# TIDA-00620_Schematic.net
KiCad netlist of a schematic drawn in Altium Designer
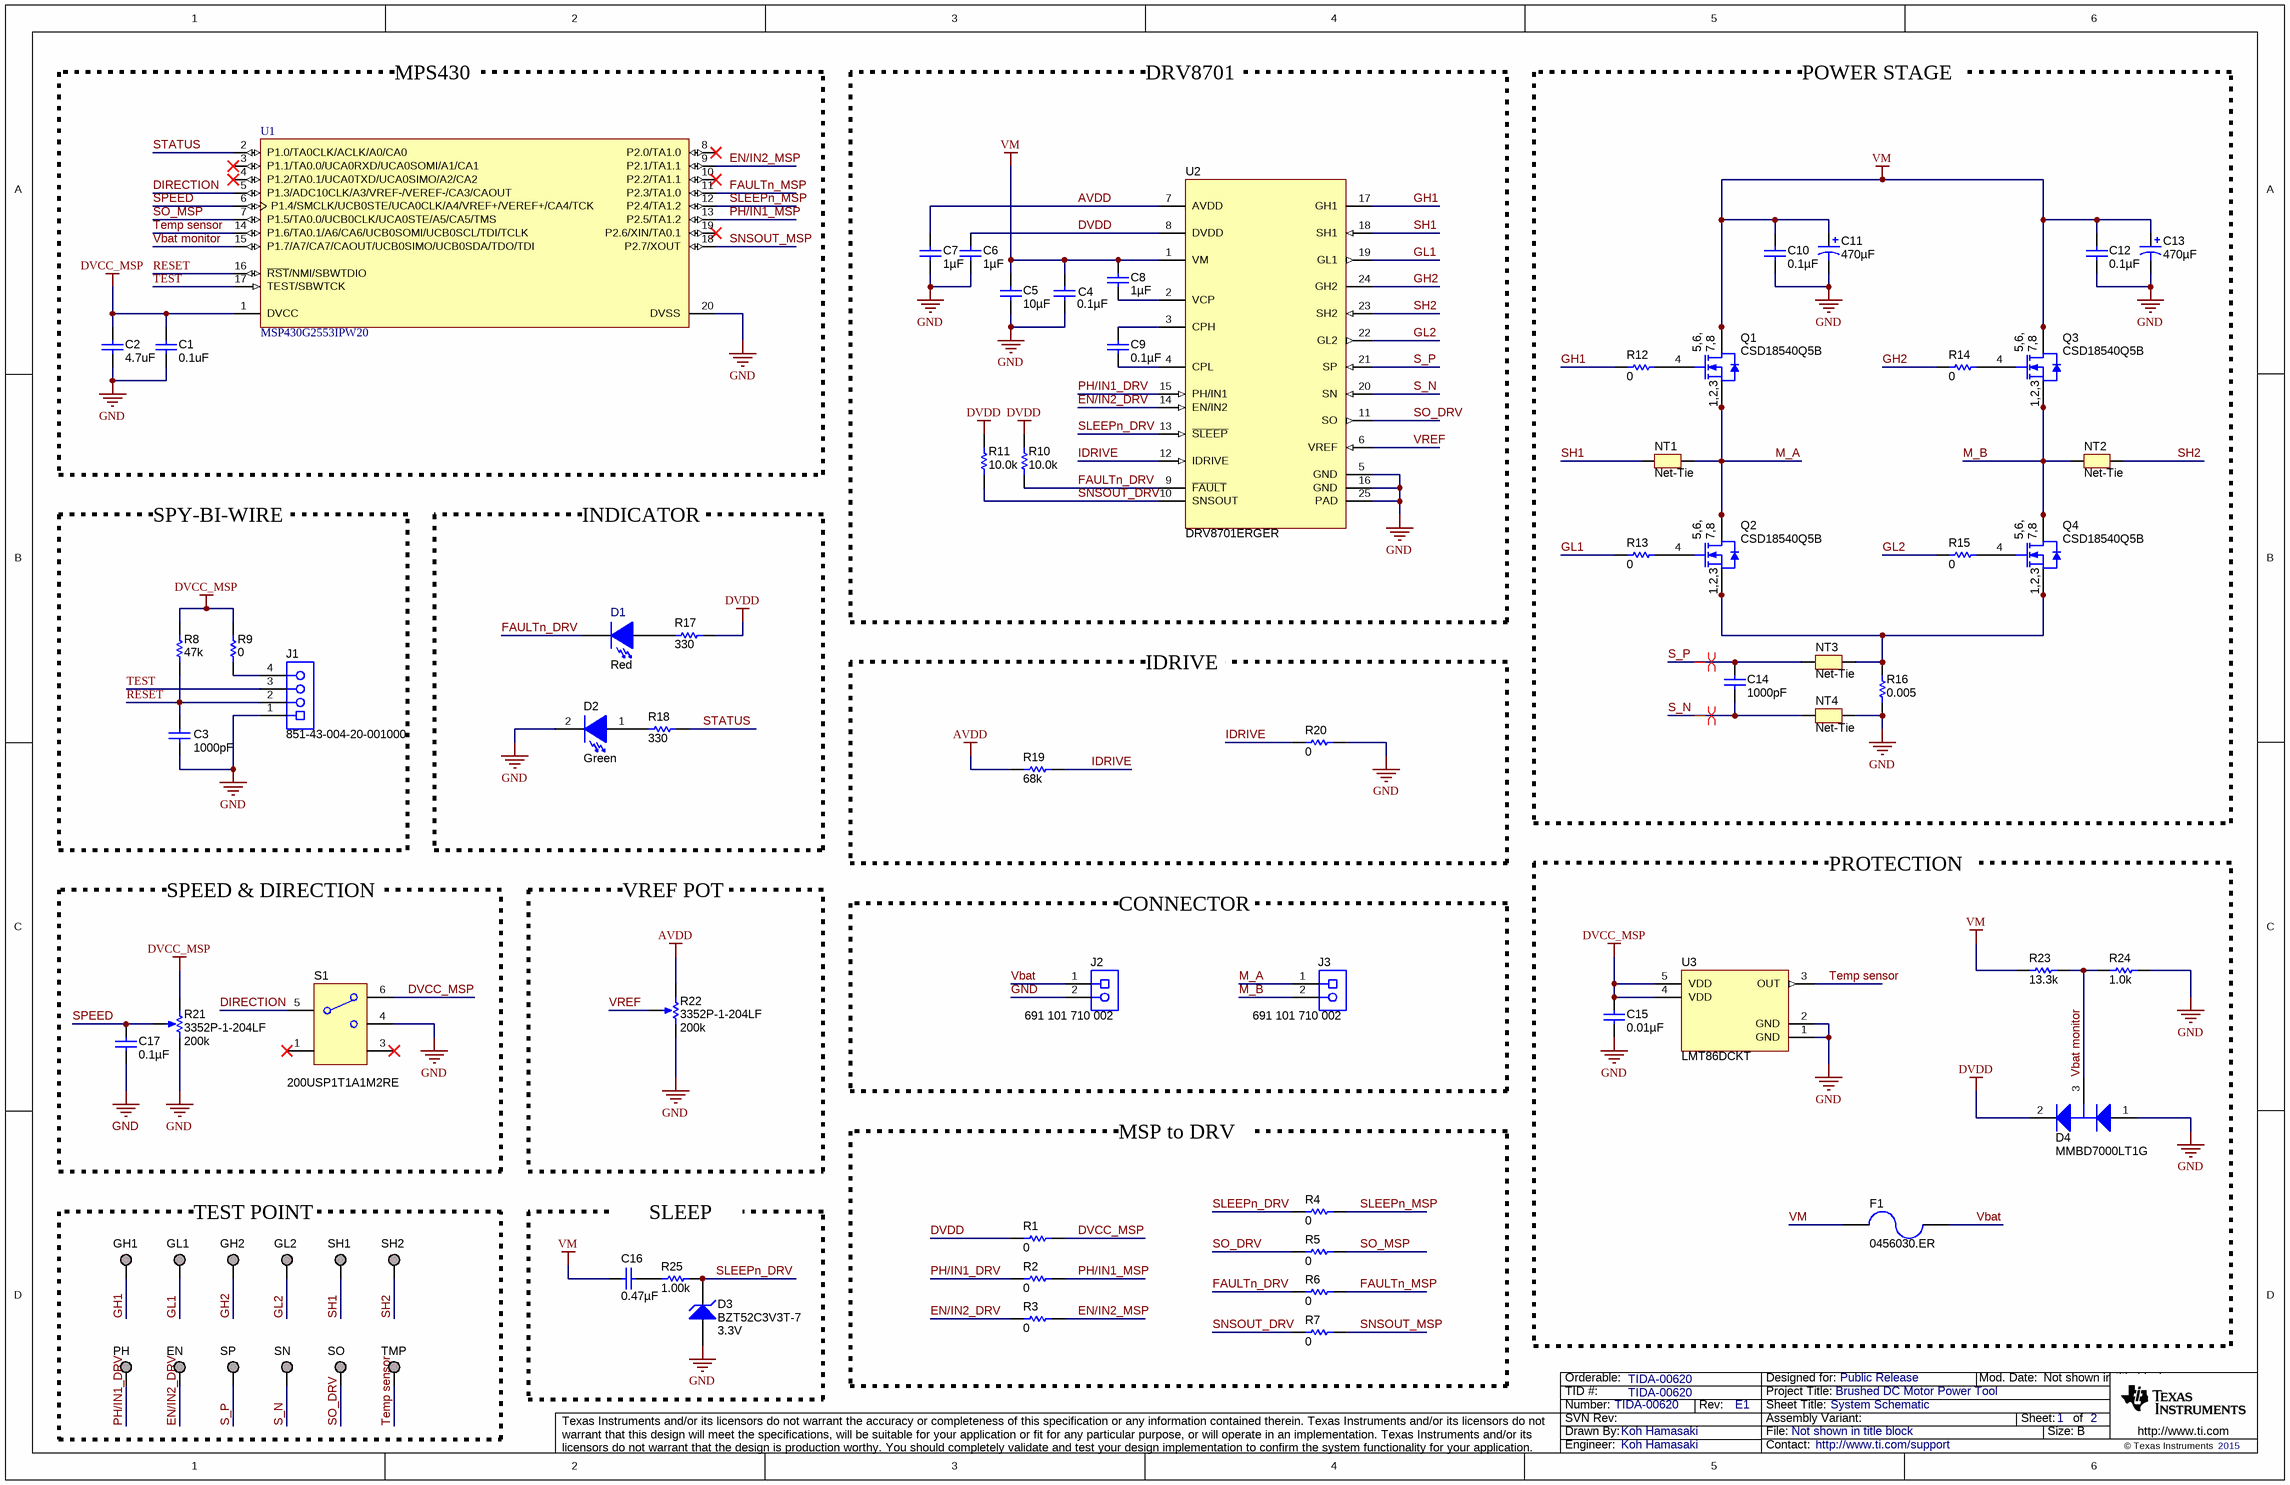
[diagram p0: TIDA-00620_Schematic.SchDoc]

(export (version "E")
  (design (tool "Eeschema 10.0.6"))
  (components
    (comp (ref "C1")
      (value "C0603C104K8RACTU")
      (footprint "0603L")
      (description "CAP, CERM, 0.1uF, 10V, +/-10%, X7R, 0603")
      (fields
        (field (name "VALUEDISPLAYED") "0.1uF")
        (field (name "MANUFACTURER") "Kemet")
        (field (name "PUBLISHER") "Texas Instruments")
      )
      (libsource (lib "Capacitor_Ceramic") (part "C0603C104K8RACTU"))
    )
    (comp (ref "C2")
      (value "C2012X7R1A475M")
      (footprint "0805L")
      (description "CAP, CERM, 4.7uF, 10V, +/-20%, X7R, 0805")
      (fields
        (field (name "VALUEDISPLAYED") "4.7uF")
        (field (name "MANUFACTURER") "TDK")
        (field (name "PUBLISHER") "Texas Instruments")
      )
      (libsource (lib "Capacitor_Ceramic") (part "C2012X7R1A475M"))
    )
    (comp (ref "C3")
      (value "GRM188R71C102KA01D")
      (footprint "0603L")
      (description "CAP, CERM, 1000pF, 16V, +/-10%, X7R, 0603")
      (fields
        (field (name "VALUEDISPLAYED") "1000pF")
        (field (name "MANUFACTURER") "MuRata")
        (field (name "PUBLISHER") "Texas Instruments")
      )
      (libsource (lib "Capacitor_Ceramic") (part "GRM188R71C102KA01D"))
    )
    (comp (ref "C4")
      (value "GRM319R71H104KA01D")
      (footprint "1206L")
      (description "CAP, CERM, 0.1 µF, 50 V, +/- 10%, X7R, 1206")
      (fields
        (field (name "VALUEDISPLAYED") "0.1µF")
        (field (name "MANUFACTURER") "MuRata")
        (field (name "PUBLISHER") "Texas Instruments")
      )
      (libsource (lib "Capacitor_Ceramic") (part "GRM319R71H104KA01D"))
    )
    (comp (ref "C5")
      (value "GRM32ER71H106KA12L")
      (footprint "1210L")
      (description "CAP, CERM, 10 µF, 50 V, +/- 10%, X7R, 1210")
      (fields
        (field (name "VALUEDISPLAYED") "10µF")
        (field (name "MANUFACTURER") "MuRata")
        (field (name "PUBLISHER") "Texas Instruments")
      )
      (libsource (lib "Capacitor_Ceramic") (part "GRM32ER71H106KA12L"))
    )
    (comp (ref "C6")
      (value "GRM188R60J105KA01D")
      (footprint "0603L")
      (description "CAP, CERM, 1 µF, 6.3 V, +/- 10%, X5R, 0603")
      (fields
        (field (name "VALUEDISPLAYED") "1µF")
        (field (name "MANUFACTURER") "MuRata")
        (field (name "PUBLISHER") "Texas Instruments")
      )
      (libsource (lib "Capacitor_Ceramic") (part "GRM188R60J105KA01D"))
    )
    (comp (ref "C7")
      (value "GRM188R60J105KA01D")
      (footprint "0603L")
      (description "CAP, CERM, 1 µF, 6.3 V, +/- 10%, X5R, 0603")
      (fields
        (field (name "VALUEDISPLAYED") "1µF")
        (field (name "MANUFACTURER") "MuRata")
        (field (name "PUBLISHER") "Texas Instruments")
      )
      (libsource (lib "Capacitor_Ceramic") (part "GRM188R60J105KA01D"))
    )
    (comp (ref "C8")
      (value "GRM319R71C105KAA3D")
      (footprint "1206L")
      (description "CAP, CERM, 1 µF, 16 V, +/- 10%, X7R, 1206")
      (fields
        (field (name "VALUEDISPLAYED") "1µF")
        (field (name "MANUFACTURER") "MuRata")
        (field (name "PUBLISHER") "Texas Instruments")
      )
      (libsource (lib "Capacitor_Ceramic") (part "GRM319R71C105KAA3D"))
    )
    (comp (ref "C9")
      (value "GRM155R71C104KA88D")
      (footprint "0402L")
      (description "CAP, CERM, 0.1 µF, 16 V, +/- 10%, X7R, 0402")
      (fields
        (field (name "VALUEDISPLAYED") "0.1µF")
        (field (name "MANUFACTURER") "MuRata")
        (field (name "PUBLISHER") "Texas Instruments")
      )
      (libsource (lib "Capacitor_Ceramic") (part "GRM155R71C104KA88D"))
    )
    (comp (ref "C10")
      (value "GRM319R71H104KA01D")
      (footprint "1206L")
      (description "CAP, CERM, 0.1 µF, 50 V, +/- 10%, X7R, 1206")
      (fields
        (field (name "VALUEDISPLAYED") "0.1µF")
        (field (name "MANUFACTURER") "MuRata")
        (field (name "PUBLISHER") "Texas Instruments")
      )
      (libsource (lib "Capacitor_Ceramic") (part "GRM319R71H104KA01D"))
    )
    (comp (ref "C11")
      (value "EEU-FR1V471LB")
      (footprint "CAPPRD350W60D800H2000")
      (description "CAP, AL, 470 µF, 35 V, +/- 20%, 0.03 ohm, TH")
      (fields
        (field (name "VALUEDISPLAYED") "470µF")
        (field (name "MANUFACTURER") "Panasonic")
        (field (name "PUBLISHER") "Texas Instruments")
      )
      (libsource (lib "Capacitor_Aluminum") (part "EEU-FR1V471LB"))
    )
    (comp (ref "C12")
      (value "GRM319R71H104KA01D")
      (footprint "1206L")
      (description "CAP, CERM, 0.1 µF, 50 V, +/- 10%, X7R, 1206")
      (fields
        (field (name "VALUEDISPLAYED") "0.1µF")
        (field (name "MANUFACTURER") "MuRata")
        (field (name "PUBLISHER") "Texas Instruments")
      )
      (libsource (lib "Capacitor_Ceramic") (part "GRM319R71H104KA01D"))
    )
    (comp (ref "C13")
      (value "EEU-FR1V471LB")
      (footprint "CAPPRD350W60D800H2000")
      (description "CAP, AL, 470 µF, 35 V, +/- 20%, 0.03 ohm, TH")
      (fields
        (field (name "VALUEDISPLAYED") "470µF")
        (field (name "MANUFACTURER") "Panasonic")
        (field (name "PUBLISHER") "Texas Instruments")
      )
      (libsource (lib "Capacitor_Aluminum") (part "EEU-FR1V471LB"))
    )
    (comp (ref "C14")
      (value "GRM155R71C102KA01D")
      (footprint "0402L")
      (description "CAP, CERM, 1000pF, 16V, +/-10%, X7R, 0402")
      (fields
        (field (name "VALUEDISPLAYED") "1000pF")
        (field (name "MANUFACTURER") "MuRata")
        (field (name "PUBLISHER") "Texas Instruments")
      )
      (libsource (lib "Capacitor_Ceramic") (part "GRM155R71C102KA01D"))
    )
    (comp (ref "C15")
      (value "GRM188R70J103KA01D")
      (footprint "0603L")
      (description "CAP, CERM, 0.01 µF, 6.3 V, +/- 10%, X7R, 0603")
      (fields
        (field (name "VALUEDISPLAYED") "0.01µF")
        (field (name "MANUFACTURER") "MuRata")
        (field (name "PUBLISHER") "Texas Instruments")
      )
      (libsource (lib "Capacitor_Ceramic") (part "GRM188R70J103KA01D"))
    )
    (comp (ref "C16")
      (value "GRM155R61A474KE15D")
      (footprint "0402L")
      (description "CAP, CERM, 0.47 µF, 10 V, +/- 10%, X5R, 0402")
      (fields
        (field (name "VALUEDISPLAYED") "0.47µF")
        (field (name "MANUFACTURER") "MuRata")
        (field (name "PUBLISHER") "Texas Instruments")
      )
      (libsource (lib "Capacitor_Ceramic") (part "GRM155R61A474KE15D"))
    )
    (comp (ref "C17")
      (value "GCM155R71C104KA55D")
      (footprint "0402")
      (description "CAP, CERM, 0.1 µF, 16 V, +/- 10%, X7R, 0402")
      (fields
        (field (name "VALUEDISPLAYED") "0.1µF")
        (field (name "MANUFACTURER") "MuRata")
        (field (name "PUBLISHER") "Texas Instruments")
      )
      (libsource (lib "Capacitor_Ceramic") (part "GCM155R71C104KA55D"))
    )
    (comp (ref "D1")
      (value "Red")
      (footprint "LED_LTST-C170")
      (description "LED, Red, SMD")
      (fields
        (field (name "MANUFACTURER") "Lite-On")
        (field (name "PARTNUMBER") "LTST-C170KRKT")
        (field (name "PUBLISHER") "Texas Instruments")
      )
      (libsource (lib "LED") (part "LTST-C170KRKT"))
    )
    (comp (ref "D2")
      (value "Green")
      (footprint "LED_LTST-C171")
      (description "LED, Green, SMD")
      (fields
        (field (name "MANUFACTURER") "Lite-On")
        (field (name "PARTNUMBER") "LTST-C171GKT")
        (field (name "PUBLISHER") "Texas Instruments")
      )
      (libsource (lib "LED") (part "LTST-C171GKT"))
    )
    (comp (ref "D3")
      (value "BZT52C3V3T-7")
      (footprint "SOD-523")
      (description "Diode, Zener, 3.3 V, 300 mW, SOD-523")
      (fields
        (field (name "ALTIUM_VALUE") "3.3V")
        (field (name "MANUFACTURER") "Diodes Inc.")
        (field (name "SYMBOLCREATOR") "a0412235")
        (field (name "PUBLISHER") "Texas Instruments")
      )
      (libsource (lib "ZenerDiodes") (part "BZT52C3V3T-7"))
    )
    (comp (ref "D4")
      (value "MMBD7000LT1G")
      (footprint "SOT-23")
      (description "Diode, Switching, 100 V, 0.2 A, SOT-23")
      (fields (field (name "MANUFACTURER") "ON Semiconductor") (field (name "PUBLISHER") "Texas Instruments"))
      (libsource (lib "Diode") (part "MMBD7000LT1G"))
    )
    (comp (ref "EN")
      (value "TESTPOINT")
      (footprint "TP_25MIL-SMT")
      (description "TEST POINT.  No entry in BOM.")
      (fields (field (name "PUBLISHER") "Texas Instruments"))
      (libsource (lib "MiscParts") (part "TESTPOINT"))
    )
    (comp (ref "F1")
      (value "0456030.ER")
      (footprint "FUSE_0456030")
      (description "Fuse, 30 A, 72 V, SMD")
      (fields (field (name "MANUFACTURER") "Littelfuse") (field (name "PUBLISHER") "Texas Instruments"))
      (libsource (lib "Fuse") (part "0456030.ER"))
    )
    (comp (ref "GH1")
      (value "TESTPOINT")
      (footprint "TP_25MIL-SMT")
      (description "TEST POINT.  No entry in BOM.")
      (fields (field (name "PUBLISHER") "Texas Instruments"))
      (libsource (lib "MiscParts") (part "TESTPOINT"))
    )
    (comp (ref "GH2")
      (value "TESTPOINT")
      (footprint "TP_25MIL-SMT")
      (description "TEST POINT.  No entry in BOM.")
      (fields (field (name "PUBLISHER") "Texas Instruments"))
      (libsource (lib "MiscParts") (part "TESTPOINT"))
    )
    (comp (ref "GL1")
      (value "TESTPOINT")
      (footprint "TP_25MIL-SMT")
      (description "TEST POINT.  No entry in BOM.")
      (fields (field (name "PUBLISHER") "Texas Instruments"))
      (libsource (lib "MiscParts") (part "TESTPOINT"))
    )
    (comp (ref "GL2")
      (value "TESTPOINT")
      (footprint "TP_25MIL-SMT")
      (description "TEST POINT.  No entry in BOM.")
      (fields (field (name "PUBLISHER") "Texas Instruments"))
      (libsource (lib "MiscParts") (part "TESTPOINT"))
    )
    (comp (ref "J1")
      (value "851-43-004-20-001000")
      (footprint "CONN_851-43-004-20-001000")
      (description "SOCKET .050\" GRID SIP 4 POS R/A, TH")
      (fields
        (field (name "MANUFACTURER") "Mill-Max")
        (field (name "SYMBOLCREATOR") "a0411947")
        (field (name "PUBLISHER") "Texas Instruments")
      )
      (libsource (lib "Connectors_Mill_Max") (part "851-43-004-20-001000"))
    )
    (comp (ref "J2")
      (value "691 101 710 002")
      (footprint "Wurth_691101710002")
      (description "Terminal Block, 5 mm, 2x1, Tin, TH")
      (fields
        (field (name "MANUFACTURER") "Wurth Elektronik")
        (field (name "SYMBOLCREATOR") "a0412235")
        (field (name "PUBLISHER") "Texas Instruments")
      )
      (libsource (lib "Connectors_Other") (part "691 101 710 002"))
    )
    (comp (ref "J3")
      (value "691 101 710 002")
      (footprint "Wurth_691101710002")
      (description "Terminal Block, 5 mm, 2x1, Tin, TH")
      (fields
        (field (name "MANUFACTURER") "Wurth Elektronik")
        (field (name "SYMBOLCREATOR") "a0412235")
        (field (name "PUBLISHER") "Texas Instruments")
      )
      (libsource (lib "Connectors_Other") (part "691 101 710 002"))
    )
    (comp (ref "NT1")
      (value "Net-Tie")
      (footprint "Net-Tie_10milWide_30milLong")
      (description "Single point connection between nets.")
      (fields (field (name "SYMBOLCREATOR") "codlsc") (field (name "PUBLISHER") "Texas Instruments"))
      (libsource (lib "MiscParts") (part "Net-Tie"))
    )
    (comp (ref "NT2")
      (value "Net-Tie")
      (footprint "Net-Tie_10milWide_30milLong")
      (description "Single point connection between nets.")
      (fields (field (name "SYMBOLCREATOR") "codlsc") (field (name "PUBLISHER") "Texas Instruments"))
      (libsource (lib "MiscParts") (part "Net-Tie"))
    )
    (comp (ref "NT3")
      (value "Net-Tie")
      (footprint "Net-Tie_10milWide_30milLong")
      (description "Single point connection between nets.")
      (fields (field (name "SYMBOLCREATOR") "codlsc") (field (name "PUBLISHER") "Texas Instruments"))
      (libsource (lib "MiscParts") (part "Net-Tie"))
    )
    (comp (ref "NT4")
      (value "Net-Tie")
      (footprint "Net-Tie_10milWide_30milLong")
      (description "Single point connection between nets.")
      (fields (field (name "SYMBOLCREATOR") "codlsc") (field (name "PUBLISHER") "Texas Instruments"))
      (libsource (lib "MiscParts") (part "Net-Tie"))
    )
    (comp (ref "PH")
      (value "TESTPOINT")
      (footprint "TP_25MIL-SMT")
      (description "TEST POINT.  No entry in BOM.")
      (fields (field (name "PUBLISHER") "Texas Instruments"))
      (libsource (lib "MiscParts") (part "TESTPOINT"))
    )
    (comp (ref "Q1")
      (value "CSD18540Q5B")
      (footprint "TRANS_NexFET_Q5B")
      (description "MOSFET, N-CH, 60 V, 28 A, SON 5x6mm")
      (fields
        (field (name "MANUFACTURER") "Texas Instruments")
        (field (name "PUBLISHER") "Texas Instruments")
      )
      (libsource (lib "FETs") (part "CSD18540Q5B"))
    )
    (comp (ref "Q2")
      (value "CSD18540Q5B")
      (footprint "TRANS_NexFET_Q5B")
      (description "MOSFET, N-CH, 60 V, 28 A, SON 5x6mm")
      (fields
        (field (name "MANUFACTURER") "Texas Instruments")
        (field (name "PUBLISHER") "Texas Instruments")
      )
      (libsource (lib "FETs") (part "CSD18540Q5B"))
    )
    (comp (ref "Q3")
      (value "CSD18540Q5B")
      (footprint "TRANS_NexFET_Q5B")
      (description "MOSFET, N-CH, 60 V, 28 A, SON 5x6mm")
      (fields
        (field (name "MANUFACTURER") "Texas Instruments")
        (field (name "PUBLISHER") "Texas Instruments")
      )
      (libsource (lib "FETs") (part "CSD18540Q5B"))
    )
    (comp (ref "Q4")
      (value "CSD18540Q5B")
      (footprint "TRANS_NexFET_Q5B")
      (description "MOSFET, N-CH, 60 V, 28 A, SON 5x6mm")
      (fields
        (field (name "MANUFACTURER") "Texas Instruments")
        (field (name "PUBLISHER") "Texas Instruments")
      )
      (libsource (lib "FETs") (part "CSD18540Q5B"))
    )
    (comp (ref "R1")
      (value "CRCW04020000Z0ED")
      (footprint "0402L")
      (description "RES, 0, 5%, 0.063 W, 0402")
      (fields
        (field (name "VALUEDISPLAYED") "0")
        (field (name "MANUFACTURER") "Vishay-Dale")
        (field (name "PUBLISHER") "Texas Instruments")
      )
      (libsource (lib "Resistor_0402") (part "CRCW04020000Z0ED"))
    )
    (comp (ref "R2")
      (value "CRCW04020000Z0ED")
      (footprint "0402L")
      (description "RES, 0, 5%, 0.063 W, 0402")
      (fields
        (field (name "VALUEDISPLAYED") "0")
        (field (name "MANUFACTURER") "Vishay-Dale")
        (field (name "PUBLISHER") "Texas Instruments")
      )
      (libsource (lib "Resistor_0402") (part "CRCW04020000Z0ED"))
    )
    (comp (ref "R3")
      (value "CRCW04020000Z0ED")
      (footprint "0402L")
      (description "RES, 0, 5%, 0.063 W, 0402")
      (fields
        (field (name "VALUEDISPLAYED") "0")
        (field (name "MANUFACTURER") "Vishay-Dale")
        (field (name "PUBLISHER") "Texas Instruments")
      )
      (libsource (lib "Resistor_0402") (part "CRCW04020000Z0ED"))
    )
    (comp (ref "R4")
      (value "CRCW04020000Z0ED")
      (footprint "0402L")
      (description "RES, 0, 5%, 0.063 W, 0402")
      (fields
        (field (name "VALUEDISPLAYED") "0")
        (field (name "MANUFACTURER") "Vishay-Dale")
        (field (name "PUBLISHER") "Texas Instruments")
      )
      (libsource (lib "Resistor_0402") (part "CRCW04020000Z0ED"))
    )
    (comp (ref "R5")
      (value "CRCW04020000Z0ED")
      (footprint "0402L")
      (description "RES, 0, 5%, 0.063 W, 0402")
      (fields
        (field (name "VALUEDISPLAYED") "0")
        (field (name "MANUFACTURER") "Vishay-Dale")
        (field (name "PUBLISHER") "Texas Instruments")
      )
      (libsource (lib "Resistor_0402") (part "CRCW04020000Z0ED"))
    )
    (comp (ref "R6")
      (value "CRCW04020000Z0ED")
      (footprint "0402L")
      (description "RES, 0, 5%, 0.063 W, 0402")
      (fields
        (field (name "VALUEDISPLAYED") "0")
        (field (name "MANUFACTURER") "Vishay-Dale")
        (field (name "PUBLISHER") "Texas Instruments")
      )
      (libsource (lib "Resistor_0402") (part "CRCW04020000Z0ED"))
    )
    (comp (ref "R7")
      (value "CRCW04020000Z0ED")
      (footprint "0402L")
      (description "RES, 0, 5%, 0.063 W, 0402")
      (fields
        (field (name "VALUEDISPLAYED") "0")
        (field (name "MANUFACTURER") "Vishay-Dale")
        (field (name "PUBLISHER") "Texas Instruments")
      )
      (libsource (lib "Resistor_0402") (part "CRCW04020000Z0ED"))
    )
    (comp (ref "R8")
      (value "47k")
      (footprint "0603L")
      (description "RES, 47k ohm, 5%, 0.1W, 0603")
      (fields
        (field (name "PARTNUMBER") "CRCW060347K0JNEA")
        (field (name "MANUFACTURER") "Vishay-Dale")
        (field (name "PUBLISHER") "Texas Instruments")
      )
      (libsource (lib "Resistor_0603") (part "CRCW060347K0JNEA"))
    )
    (comp (ref "R9")
      (value "0")
      (footprint "0603L")
      (description "RES, 0 ohm, 5%, 0.1W, 0603")
      (fields
        (field (name "PARTNUMBER") "CRCW06030000Z0EA")
        (field (name "MANUFACTURER") "Vishay-Dale")
        (field (name "PUBLISHER") "Texas Instruments")
      )
      (libsource (lib "Resistor_0603") (part "CRCW06030000Z0EA"))
    )
    (comp (ref "R10")
      (value "ERJ-2RKF1002X")
      (footprint "0402L")
      (description "RES, 10.0 k, 1%, 0.1 W, 0402")
      (fields
        (field (name "VALUEDISPLAYED") "10.0k")
        (field (name "MANUFACTURER") "Panasonic")
        (field (name "PUBLISHER") "Texas Instruments")
      )
      (libsource (lib "Resistor_0402") (part "ERJ-2RKF1002X"))
    )
    (comp (ref "R11")
      (value "ERJ-2RKF1002X")
      (footprint "0402L")
      (description "RES, 10.0 k, 1%, 0.1 W, 0402")
      (fields
        (field (name "VALUEDISPLAYED") "10.0k")
        (field (name "MANUFACTURER") "Panasonic")
        (field (name "PUBLISHER") "Texas Instruments")
      )
      (libsource (lib "Resistor_0402") (part "ERJ-2RKF1002X"))
    )
    (comp (ref "R12")
      (value "CRCW04020000Z0ED")
      (footprint "0402L")
      (description "RES, 0, 5%, 0.063 W, 0402")
      (fields
        (field (name "VALUEDISPLAYED") "0")
        (field (name "MANUFACTURER") "Vishay-Dale")
        (field (name "PUBLISHER") "Texas Instruments")
      )
      (libsource (lib "Resistor_0402") (part "CRCW04020000Z0ED"))
    )
    (comp (ref "R13")
      (value "CRCW04020000Z0ED")
      (footprint "0402L")
      (description "RES, 0, 5%, 0.063 W, 0402")
      (fields
        (field (name "VALUEDISPLAYED") "0")
        (field (name "MANUFACTURER") "Vishay-Dale")
        (field (name "PUBLISHER") "Texas Instruments")
      )
      (libsource (lib "Resistor_0402") (part "CRCW04020000Z0ED"))
    )
    (comp (ref "R14")
      (value "CRCW04020000Z0ED")
      (footprint "0402L")
      (description "RES, 0, 5%, 0.063 W, 0402")
      (fields
        (field (name "VALUEDISPLAYED") "0")
        (field (name "MANUFACTURER") "Vishay-Dale")
        (field (name "PUBLISHER") "Texas Instruments")
      )
      (libsource (lib "Resistor_0402") (part "CRCW04020000Z0ED"))
    )
    (comp (ref "R15")
      (value "CRCW04020000Z0ED")
      (footprint "0402L")
      (description "RES, 0, 5%, 0.063 W, 0402")
      (fields
        (field (name "VALUEDISPLAYED") "0")
        (field (name "MANUFACTURER") "Vishay-Dale")
        (field (name "PUBLISHER") "Texas Instruments")
      )
      (libsource (lib "Resistor_0402") (part "CRCW04020000Z0ED"))
    )
    (comp (ref "R16")
      (value "KRL11050-C-R005-F-T1")
      (footprint "4320")
      (description "RES, 0.005, 1%, 6 W, 4320_WIDE")
      (fields
        (field (name "VALUEDISPLAYED") "0.005")
        (field (name "MANUFACTURER") "Susumu Co Ltd")
        (field (name "PUBLISHER") "Texas Instruments")
      )
      (libsource (lib "Resistor_OtherSMT") (part "KRL11050-C-R005-F-T1"))
    )
    (comp (ref "R17")
      (value "RC0603FR-07330RL")
      (footprint "0603L")
      (description "RES, 330, 1%, 0.1 W, 0603")
      (fields
        (field (name "VALUEDISPLAYED") "330")
        (field (name "MANUFACTURER") "Yageo America")
        (field (name "PUBLISHER") "Texas Instruments")
      )
      (libsource (lib "Resistor_0603") (part "RC0603FR-07330RL"))
    )
    (comp (ref "R18")
      (value "RC0603FR-07330RL")
      (footprint "0603L")
      (description "RES, 330, 1%, 0.1 W, 0603")
      (fields
        (field (name "VALUEDISPLAYED") "330")
        (field (name "MANUFACTURER") "Yageo America")
        (field (name "PUBLISHER") "Texas Instruments")
      )
      (libsource (lib "Resistor_0603") (part "RC0603FR-07330RL"))
    )
    (comp (ref "R19")
      (value "CRCW040268K0JNED")
      (footprint "0402")
      (description "RES, 68 k, 5%, 0.063 W, 0402")
      (fields
        (field (name "VALUEDISPLAYED") "68k")
        (field (name "MANUFACTURER") "Vishay-Dale")
        (field (name "PUBLISHER") "Texas Instruments")
      )
      (libsource (lib "Resistor_0402") (part "CRCW040268K0JNED"))
    )
    (comp (ref "R20")
      (value "CRCW04020000Z0ED")
      (footprint "0402L")
      (description "RES, 0, 5%, 0.063 W, 0402")
      (fields
        (field (name "VALUEDISPLAYED") "0")
        (field (name "MANUFACTURER") "Vishay-Dale")
        (field (name "PUBLISHER") "Texas Instruments")
      )
      (libsource (lib "Resistor_0402") (part "CRCW04020000Z0ED"))
    )
    (comp (ref "R21")
      (value "3352P-1-204LF")
      (footprint "Bourns_3352P")
      (description "Trimmer, 200 K, 0.5 W, TH")
      (fields
        (field (name "ALTIUM_VALUE") "200k")
        (field (name "MANUFACTURER") "Bourns")
        (field (name "SYMBOLCREATOR") "a0412235")
        (field (name "PUBLISHER") "Texas Instruments")
      )
      (libsource (lib "Other_Passive") (part "3352P-1-204LF"))
    )
    (comp (ref "R22")
      (value "3352P-1-204LF")
      (footprint "Bourns_3352P")
      (description "Trimmer, 200 K, 0.5 W, TH")
      (fields
        (field (name "ALTIUM_VALUE") "200k")
        (field (name "MANUFACTURER") "Bourns")
        (field (name "SYMBOLCREATOR") "a0412235")
        (field (name "PUBLISHER") "Texas Instruments")
      )
      (libsource (lib "Other_Passive") (part "3352P-1-204LF"))
    )
    (comp (ref "R23")
      (value "CRCW040213K3FKED")
      (footprint "0402L")
      (description "RES, 13.3 k, 1%, 0.063 W, 0402")
      (fields
        (field (name "VALUEDISPLAYED") "13.3k")
        (field (name "MANUFACTURER") "Vishay-Dale")
        (field (name "PUBLISHER") "Texas Instruments")
      )
      (libsource (lib "Resistor_0402") (part "CRCW040213K3FKED"))
    )
    (comp (ref "R24")
      (value "CRCW04021K00JNED")
      (footprint "0402L")
      (description "RES, 1.0 k, 5%, 0.063 W, 0402")
      (fields
        (field (name "VALUEDISPLAYED") "1.0k")
        (field (name "MANUFACTURER") "Vishay-Dale")
        (field (name "PUBLISHER") "Texas Instruments")
      )
      (libsource (lib "Resistor_0402") (part "CRCW04021K00JNED"))
    )
    (comp (ref "R25")
      (value "CRCW04021K00FKED")
      (footprint "0402L")
      (description "RES, 1.00 k, 1%, 0.063 W, 0402")
      (fields
        (field (name "MANUFACTURER") "Vishay-Dale")
        (field (name "VALUEDISPLAYED") "1.00k")
        (field (name "PUBLISHER") "Texas Instruments")
      )
      (libsource (lib "Resistor_0402") (part "CRCW04021K00FKED"))
    )
    (comp (ref "S1")
      (value "200USP1T1A1M2RE")
      (footprint "SW_200USP1T1A1M2")
      (description "Switch, SPDT, On-On, 2 Pos, TH")
      (fields
        (field (name "MANUFACTURER") "E-Switch")
        (field (name "SYMBOLCREATOR") "Altium")
        (field (name "PUBLISHER") "Texas Instruments")
      )
      (libsource (lib "Switches") (part "200USP1T1A1M2RE"))
    )
    (comp (ref "SH1")
      (value "TESTPOINT")
      (footprint "TP_25MIL-SMT")
      (description "TEST POINT.  No entry in BOM.")
      (fields (field (name "PUBLISHER") "Texas Instruments"))
      (libsource (lib "MiscParts") (part "TESTPOINT"))
    )
    (comp (ref "SH2")
      (value "TESTPOINT")
      (footprint "TP_25MIL-SMT")
      (description "TEST POINT.  No entry in BOM.")
      (fields (field (name "PUBLISHER") "Texas Instruments"))
      (libsource (lib "MiscParts") (part "TESTPOINT"))
    )
    (comp (ref "SN")
      (value "TESTPOINT")
      (footprint "TP_25MIL-SMT")
      (description "TEST POINT.  No entry in BOM.")
      (fields (field (name "PUBLISHER") "Texas Instruments"))
      (libsource (lib "MiscParts") (part "TESTPOINT"))
    )
    (comp (ref "SO")
      (value "TESTPOINT")
      (footprint "TP_25MIL-SMT")
      (description "TEST POINT.  No entry in BOM.")
      (fields (field (name "PUBLISHER") "Texas Instruments"))
      (libsource (lib "MiscParts") (part "TESTPOINT"))
    )
    (comp (ref "SP")
      (value "TESTPOINT")
      (footprint "TP_25MIL-SMT")
      (description "TEST POINT.  No entry in BOM.")
      (fields (field (name "PUBLISHER") "Texas Instruments"))
      (libsource (lib "MiscParts") (part "TESTPOINT"))
    )
    (comp (ref "TMP")
      (value "TESTPOINT")
      (footprint "TP_25MIL-SMT")
      (description "TEST POINT.  No entry in BOM.")
      (fields (field (name "PUBLISHER") "Texas Instruments"))
      (libsource (lib "MiscParts") (part "TESTPOINT"))
    )
    (comp (ref "U1")
      (value "MSP430G2553IPW20")
      (footprint "PW0020A_N")
      (fields
        (field (name "ALTERNATE PARTNUMBER") "Equivalent")
        (field (name "MANUFACTURER") "Texas Instruments")
      )
      (libsource (lib "TI MCU MSP430") (part "MSP430G2553IPW20"))
    )
    (comp (ref "U2")
      (value "DRV8701ERGER")
      (footprint "RGE0024F")
      (description "H-Bridge Gate Driver, RGE0024F")
      (fields
        (field (name "ALTERNATE PARTNUMBER") "DRV8701ERGET")
        (field (name "MANUFACTURER") "Texas Instruments")
        (field (name "SYMBOLCREATOR") "Altium")
        (field (name "PUBLISHER") "Texas Instruments")
      )
      (libsource (lib "TI_Pre_RTM") (part "DRV8701ERGER"))
    )
    (comp (ref "U3")
      (value "LMT86DCKT")
      (footprint "DCK0005A_N")
      (description "Analog Temperature Sensors with Class-AB Output, DCK0005A")
      (fields
        (field (name "MANUFACTURER") "Texas Instruments")
        (field (name "SYMBOLCREATOR") "a0799628")
        (field (name "PUBLISHER") "Texas Instruments")
      )
      (libsource (lib "TI_Pre_Release") (part "LMT86DCKT"))
    )
  )
  (nets
    (net (code "1") (name "/DIRECTION") (class "Default")
      (node (ref "S1") (pin "5") (pinfunction "COM_5") (pintype "passive"))
      (node (ref "U1") (pin "5") (pinfunction "P1.3/ADC10CLK/A3/VREF-/VEREF-/CA3/CAOUT_5") (pintype "bidirectional"))
    )
    (net (code "2") (name "/EN{slash}IN2_DRV") (class "Default")
      (node (ref "EN") (pin "1") (pintype "passive"))
      (node (ref "R3") (pin "1") (pinfunction "1_1") (pintype "passive"))
      (node (ref "U2") (pin "14") (pinfunction "EN/IN2_14") (pintype "input"))
    )
    (net (code "3") (name "/EN{slash}IN2_MSP") (class "Default")
      (node (ref "R3") (pin "2") (pinfunction "2_2") (pintype "passive"))
      (node (ref "U1") (pin "9") (pinfunction "P2.1/TA1.1_9") (pintype "bidirectional"))
    )
    (net (code "4") (name "/FAULTn_DRV") (class "Default")
      (node (ref "D1") (pin "2") (pinfunction "K_2") (pintype "passive"))
      (node (ref "R10") (pin "1") (pinfunction "1_1") (pintype "passive"))
      (node (ref "R6") (pin "1") (pinfunction "1_1") (pintype "passive"))
      (node (ref "U2") (pin "9") (pinfunction "FAULT_9") (pintype "open_collector"))
    )
    (net (code "5") (name "/FAULTn_MSP") (class "Default")
      (node (ref "R6") (pin "2") (pinfunction "2_2") (pintype "passive"))
      (node (ref "U1") (pin "11") (pinfunction "P2.3/TA1.0_11") (pintype "bidirectional"))
    )
    (net (code "6") (name "/GH1") (class "Default")
      (node (ref "GH1") (pin "1") (pintype "passive"))
      (node (ref "R12") (pin "1") (pinfunction "1_1") (pintype "passive"))
      (node (ref "U2") (pin "17") (pinfunction "GH1_17") (pintype "power_in"))
    )
    (net (code "7") (name "/GH2") (class "Default")
      (node (ref "GH2") (pin "1") (pintype "passive"))
      (node (ref "R14") (pin "1") (pinfunction "1_1") (pintype "passive"))
      (node (ref "U2") (pin "24") (pinfunction "GH2_24") (pintype "power_in"))
    )
    (net (code "8") (name "/GL1") (class "Default")
      (node (ref "GL1") (pin "1") (pintype "passive"))
      (node (ref "R13") (pin "1") (pinfunction "1_1") (pintype "passive"))
      (node (ref "U2") (pin "19") (pinfunction "GL1_19") (pintype "output"))
    )
    (net (code "9") (name "/GL2") (class "Default")
      (node (ref "GL2") (pin "1") (pintype "passive"))
      (node (ref "R15") (pin "1") (pinfunction "1_1") (pintype "passive"))
      (node (ref "U2") (pin "22") (pinfunction "GL2_22") (pintype "output"))
    )
    (net (code "10") (name "/IDRIVE") (class "Default")
      (node (ref "R19") (pin "2") (pinfunction "2_2") (pintype "passive"))
      (node (ref "R20") (pin "1") (pinfunction "1_1") (pintype "passive"))
      (node (ref "U2") (pin "12") (pinfunction "IDRIVE_12") (pintype "input"))
    )
    (net (code "11") (name "/M_A") (class "Default")
      (node (ref "J3") (pin "1") (pinfunction "1_1") (pintype "passive"))
      (node (ref "NT1") (pin "2") (pinfunction "2_2") (pintype "passive"))
      (node (ref "Q1") (pin "1") (pinfunction "S_1") (pintype "passive"))
      (node (ref "Q1") (pin "2") (pinfunction "S_2") (pintype "passive"))
      (node (ref "Q1") (pin "3") (pinfunction "S_3") (pintype "passive"))
      (node (ref "Q2") (pin "5") (pinfunction "D_5") (pintype "passive"))
      (node (ref "Q2") (pin "6") (pinfunction "D_6") (pintype "passive"))
      (node (ref "Q2") (pin "7") (pinfunction "D_7") (pintype "passive"))
      (node (ref "Q2") (pin "8") (pinfunction "D_8") (pintype "passive"))
    )
    (net (code "12") (name "/M_B") (class "Default")
      (node (ref "J3") (pin "2") (pinfunction "2_2") (pintype "passive"))
      (node (ref "NT2") (pin "1") (pinfunction "1_1") (pintype "passive"))
      (node (ref "Q3") (pin "1") (pinfunction "S_1") (pintype "passive"))
      (node (ref "Q3") (pin "2") (pinfunction "S_2") (pintype "passive"))
      (node (ref "Q3") (pin "3") (pinfunction "S_3") (pintype "passive"))
      (node (ref "Q4") (pin "5") (pinfunction "D_5") (pintype "passive"))
      (node (ref "Q4") (pin "6") (pinfunction "D_6") (pintype "passive"))
      (node (ref "Q4") (pin "7") (pinfunction "D_7") (pintype "passive"))
      (node (ref "Q4") (pin "8") (pinfunction "D_8") (pintype "passive"))
    )
    (net (code "13") (name "/PH{slash}IN1_DRV") (class "Default")
      (node (ref "PH") (pin "1") (pintype "passive"))
      (node (ref "R2") (pin "1") (pinfunction "1_1") (pintype "passive"))
      (node (ref "U2") (pin "15") (pinfunction "PH/IN1_15") (pintype "input"))
    )
    (net (code "14") (name "/PH{slash}IN1_MSP") (class "Default")
      (node (ref "R2") (pin "2") (pinfunction "2_2") (pintype "passive"))
      (node (ref "U1") (pin "13") (pinfunction "P2.5/TA1.2_13") (pintype "bidirectional"))
    )
    (net (code "15") (name "/RESET") (class "Default")
      (node (ref "C3") (pin "1") (pinfunction "1_1") (pintype "passive"))
      (node (ref "J1") (pin "2") (pinfunction "2_2") (pintype "passive"))
      (node (ref "R8") (pin "1") (pinfunction "1_1") (pintype "passive"))
      (node (ref "U1") (pin "16") (pinfunction "~{RST}/NMI/SBWTDIO_16") (pintype "bidirectional"))
    )
    (net (code "16") (name "/SH1") (class "Default")
      (node (ref "NT1") (pin "1") (pinfunction "1_1") (pintype "passive"))
      (node (ref "SH1") (pin "1") (pintype "passive"))
      (node (ref "U2") (pin "18") (pinfunction "SH1_18") (pintype "input"))
    )
    (net (code "17") (name "/SH2") (class "Default")
      (node (ref "NT2") (pin "2") (pinfunction "2_2") (pintype "passive"))
      (node (ref "SH2") (pin "1") (pintype "passive"))
      (node (ref "U2") (pin "23") (pinfunction "SH2_23") (pintype "input"))
    )
    (net (code "18") (name "/SLEEPn_DRV") (class "Default")
      (node (ref "D3") (pin "1") (pinfunction "K_1") (pintype "passive"))
      (node (ref "R25") (pin "2") (pinfunction "2_2") (pintype "passive"))
      (node (ref "R4") (pin "1") (pinfunction "1_1") (pintype "passive"))
      (node (ref "U2") (pin "13") (pinfunction "SLEEP_13") (pintype "input"))
    )
    (net (code "19") (name "/SLEEPn_MSP") (class "Default")
      (node (ref "R4") (pin "2") (pinfunction "2_2") (pintype "passive"))
      (node (ref "U1") (pin "12") (pinfunction "P2.4/TA1.2_12") (pintype "bidirectional"))
    )
    (net (code "20") (name "/SNSOUT_DRV") (class "Default")
      (node (ref "R11") (pin "1") (pinfunction "1_1") (pintype "passive"))
      (node (ref "R7") (pin "1") (pinfunction "1_1") (pintype "passive"))
      (node (ref "U2") (pin "10") (pinfunction "SNSOUT_10") (pintype "open_collector"))
    )
    (net (code "21") (name "/SNSOUT_MSP") (class "Default")
      (node (ref "R7") (pin "2") (pinfunction "2_2") (pintype "passive"))
      (node (ref "U1") (pin "18") (pinfunction "P2.7/XOUT_18") (pintype "bidirectional"))
    )
    (net (code "22") (name "/SO_DRV") (class "Default")
      (node (ref "R5") (pin "1") (pinfunction "1_1") (pintype "passive"))
      (node (ref "SO") (pin "1") (pintype "passive"))
      (node (ref "U2") (pin "11") (pinfunction "SO_11") (pintype "output"))
    )
    (net (code "23") (name "/SO_MSP") (class "Default")
      (node (ref "R5") (pin "2") (pinfunction "2_2") (pintype "passive"))
      (node (ref "U1") (pin "7") (pinfunction "P1.5/TA0.0/UCB0CLK/UCA0STE/A5/CA5/TMS_7") (pintype "bidirectional"))
    )
    (net (code "24") (name "/SPEED") (class "Default")
      (node (ref "C17") (pin "1") (pinfunction "1_1") (pintype "passive"))
      (node (ref "R21") (pin "2") (pinfunction "WIPER_2") (pintype "passive"))
      (node (ref "U1") (pin "6") (pinfunction "P1.4/SMCLK/UCB0STE/UCA0CLK/A4/VREF+/VEREF+/CA4/TCK_6") (pintype "bidirectional"))
    )
    (net (code "25") (name "/STATUS") (class "Default")
      (node (ref "R18") (pin "2") (pinfunction "2_2") (pintype "passive"))
      (node (ref "U1") (pin "2") (pinfunction "P1.0/TA0CLK/ACLK/A0/CA0_2") (pintype "bidirectional"))
    )
    (net (code "26") (name "/S_N") (class "Default")
      (node (ref "C14") (pin "2") (pinfunction "2_2") (pintype "passive"))
      (node (ref "NT4") (pin "1") (pinfunction "1_1") (pintype "passive"))
      (node (ref "SN") (pin "1") (pintype "passive"))
      (node (ref "U2") (pin "20") (pinfunction "SN_20") (pintype "input"))
    )
    (net (code "27") (name "/S_P") (class "Default")
      (node (ref "C14") (pin "1") (pinfunction "1_1") (pintype "passive"))
      (node (ref "NT3") (pin "1") (pinfunction "1_1") (pintype "passive"))
      (node (ref "SP") (pin "1") (pintype "passive"))
      (node (ref "U2") (pin "21") (pinfunction "SP_21") (pintype "input"))
    )
    (net (code "28") (name "/TEST") (class "Default")
      (node (ref "J1") (pin "3") (pinfunction "3_3") (pintype "passive"))
      (node (ref "U1") (pin "17") (pinfunction "TEST/SBWTCK_17") (pintype "input"))
    )
    (net (code "29") (name "/Temp sensor") (class "Default")
      (node (ref "TMP") (pin "1") (pintype "passive"))
      (node (ref "U1") (pin "14") (pinfunction "P1.6/TA0.1/A6/CA6/UCB0SOMI/UCB0SCL/TDI/TCLK_14") (pintype "bidirectional"))
      (node (ref "U3") (pin "3") (pinfunction "OUT_3") (pintype "output"))
    )
    (net (code "30") (name "/VREF") (class "Default")
      (node (ref "R22") (pin "2") (pinfunction "WIPER_2") (pintype "passive"))
      (node (ref "U2") (pin "6") (pinfunction "VREF_6") (pintype "input"))
    )
    (net (code "31") (name "/Vbat") (class "Default")
      (node (ref "F1") (pin "1") (pinfunction "1_1") (pintype "passive"))
      (node (ref "J2") (pin "1") (pinfunction "1_1") (pintype "passive"))
    )
    (net (code "32") (name "/Vbat monitor") (class "Default")
      (node (ref "D4") (pin "3") (pinfunction "C_3") (pintype "passive"))
      (node (ref "R23") (pin "2") (pinfunction "2_2") (pintype "passive"))
      (node (ref "R24") (pin "1") (pinfunction "1_1") (pintype "passive"))
      (node (ref "U1") (pin "15") (pinfunction "P1.7/A7/CA7/CAOUT/UCB0SIMO/UCB0SDA/TDO/TDI_15") (pintype "bidirectional"))
    )
    (net (code "33") (name "AVDD") (class "Default")
      (node (ref "C7") (pin "1") (pinfunction "1_1") (pintype "passive"))
      (node (ref "R19") (pin "1") (pinfunction "1_1") (pintype "passive"))
      (node (ref "R22") (pin "1") (pinfunction "CCW_1") (pintype "passive"))
      (node (ref "U2") (pin "7") (pinfunction "AVDD_7") (pintype "power_in"))
    )
    (net (code "34") (name "DVCC_MSP") (class "Default")
      (node (ref "C1") (pin "1") (pinfunction "1_1") (pintype "passive"))
      (node (ref "C15") (pin "1") (pinfunction "1_1") (pintype "passive"))
      (node (ref "C2") (pin "1") (pinfunction "1_1") (pintype "passive"))
      (node (ref "R1") (pin "2") (pinfunction "2_2") (pintype "passive"))
      (node (ref "R21") (pin "1") (pinfunction "CCW_1") (pintype "passive"))
      (node (ref "R8") (pin "2") (pinfunction "2_2") (pintype "passive"))
      (node (ref "R9") (pin "2") (pinfunction "2_2") (pintype "passive"))
      (node (ref "S1") (pin "6") (pintype "passive"))
      (node (ref "U1") (pin "1") (pinfunction "DVCC_1") (pintype "power_in"))
      (node (ref "U3") (pin "4") (pinfunction "VDD_4") (pintype "power_in"))
      (node (ref "U3") (pin "5") (pinfunction "VDD_5") (pintype "power_in"))
    )
    (net (code "35") (name "DVDD") (class "Default")
      (node (ref "C6") (pin "1") (pinfunction "1_1") (pintype "passive"))
      (node (ref "D4") (pin "2") (pinfunction "K_2") (pintype "passive"))
      (node (ref "R1") (pin "1") (pinfunction "1_1") (pintype "passive"))
      (node (ref "R10") (pin "2") (pinfunction "2_2") (pintype "passive"))
      (node (ref "R11") (pin "2") (pinfunction "2_2") (pintype "passive"))
      (node (ref "R17") (pin "2") (pinfunction "2_2") (pintype "passive"))
      (node (ref "U2") (pin "8") (pinfunction "DVDD_8") (pintype "power_in"))
    )
    (net (code "36") (name "GND") (class "Default")
      (node (ref "C1") (pin "2") (pinfunction "2_2") (pintype "passive"))
      (node (ref "C10") (pin "2") (pinfunction "2_2") (pintype "passive"))
      (node (ref "C11") (pin "2") (pinfunction "-_2") (pintype "passive"))
      (node (ref "C12") (pin "2") (pinfunction "2_2") (pintype "passive"))
      (node (ref "C13") (pin "2") (pinfunction "-_2") (pintype "passive"))
      (node (ref "C15") (pin "2") (pinfunction "2_2") (pintype "passive"))
      (node (ref "C17") (pin "2") (pinfunction "2_2") (pintype "passive"))
      (node (ref "C2") (pin "2") (pinfunction "2_2") (pintype "passive"))
      (node (ref "C3") (pin "2") (pinfunction "2_2") (pintype "passive"))
      (node (ref "C4") (pin "2") (pinfunction "2_2") (pintype "passive"))
      (node (ref "C5") (pin "2") (pinfunction "2_2") (pintype "passive"))
      (node (ref "C6") (pin "2") (pinfunction "2_2") (pintype "passive"))
      (node (ref "C7") (pin "2") (pinfunction "2_2") (pintype "passive"))
      (node (ref "D2") (pin "2") (pinfunction "K_2") (pintype "passive"))
      (node (ref "D3") (pin "2") (pinfunction "A_2") (pintype "passive"))
      (node (ref "D4") (pin "1") (pinfunction "A_1") (pintype "passive"))
      (node (ref "J1") (pin "1") (pinfunction "1_1") (pintype "passive"))
      (node (ref "J2") (pin "2") (pinfunction "2_2") (pintype "passive"))
      (node (ref "NT4") (pin "2") (pinfunction "2_2") (pintype "passive"))
      (node (ref "R16") (pin "1") (pinfunction "1_1") (pintype "passive"))
      (node (ref "R20") (pin "2") (pinfunction "2_2") (pintype "passive"))
      (node (ref "R21") (pin "3") (pinfunction "CW_3") (pintype "passive"))
      (node (ref "R22") (pin "3") (pinfunction "CW_3") (pintype "passive"))
      (node (ref "R24") (pin "2") (pinfunction "2_2") (pintype "passive"))
      (node (ref "S1") (pin "4") (pintype "passive"))
      (node (ref "U1") (pin "20") (pinfunction "DVSS_20") (pintype "power_in"))
      (node (ref "U2") (pin "16") (pinfunction "GND_16") (pintype "power_in"))
      (node (ref "U2") (pin "25") (pinfunction "PAD_25") (pintype "power_in"))
      (node (ref "U2") (pin "5") (pinfunction "GND_5") (pintype "power_in"))
      (node (ref "U3") (pin "1") (pinfunction "GND_1") (pintype "power_in"))
      (node (ref "U3") (pin "2") (pinfunction "GND_2") (pintype "power_in"))
    )
    (net (code "37") (name "Net-(C16-Pad1)") (class "Default")
      (node (ref "C16") (pin "1") (pinfunction "1_1") (pintype "passive"))
      (node (ref "R25") (pin "1") (pinfunction "1_1") (pintype "passive"))
    )
    (net (code "38") (name "Net-(D1-A)") (class "Default")
      (node (ref "D1") (pin "1") (pinfunction "A_1") (pintype "passive"))
      (node (ref "R17") (pin "1") (pinfunction "1_1") (pintype "passive"))
    )
    (net (code "39") (name "Net-(D2-A)") (class "Default")
      (node (ref "D2") (pin "1") (pinfunction "A_1") (pintype "passive"))
      (node (ref "R18") (pin "1") (pinfunction "1_1") (pintype "passive"))
    )
    (net (code "40") (name "Net-(J1-Pad4)") (class "Default")
      (node (ref "J1") (pin "4") (pinfunction "4_4") (pintype "passive"))
      (node (ref "R9") (pin "1") (pinfunction "1_1") (pintype "passive"))
    )
    (net (code "41") (name "Net-(NT3-Pad2)") (class "Default")
      (node (ref "NT3") (pin "2") (pinfunction "2_2") (pintype "passive"))
      (node (ref "Q2") (pin "1") (pinfunction "S_1") (pintype "passive"))
      (node (ref "Q2") (pin "2") (pinfunction "S_2") (pintype "passive"))
      (node (ref "Q2") (pin "3") (pinfunction "S_3") (pintype "passive"))
      (node (ref "Q4") (pin "1") (pinfunction "S_1") (pintype "passive"))
      (node (ref "Q4") (pin "2") (pinfunction "S_2") (pintype "passive"))
      (node (ref "Q4") (pin "3") (pinfunction "S_3") (pintype "passive"))
      (node (ref "R16") (pin "2") (pinfunction "2_2") (pintype "passive"))
    )
    (net (code "42") (name "Net-(Q1-G)") (class "Default")
      (node (ref "Q1") (pin "4") (pinfunction "G_4") (pintype "passive"))
      (node (ref "R12") (pin "2") (pinfunction "2_2") (pintype "passive"))
    )
    (net (code "43") (name "Net-(Q2-G)") (class "Default")
      (node (ref "Q2") (pin "4") (pinfunction "G_4") (pintype "passive"))
      (node (ref "R13") (pin "2") (pinfunction "2_2") (pintype "passive"))
    )
    (net (code "44") (name "Net-(Q3-G)") (class "Default")
      (node (ref "Q3") (pin "4") (pinfunction "G_4") (pintype "passive"))
      (node (ref "R14") (pin "2") (pinfunction "2_2") (pintype "passive"))
    )
    (net (code "45") (name "Net-(Q4-G)") (class "Default")
      (node (ref "Q4") (pin "4") (pinfunction "G_4") (pintype "passive"))
      (node (ref "R15") (pin "2") (pinfunction "2_2") (pintype "passive"))
    )
    (net (code "46") (name "Net-(U2-CPH)") (class "Default")
      (node (ref "C9") (pin "1") (pinfunction "1_1") (pintype "passive"))
      (node (ref "U2") (pin "3") (pinfunction "CPH_3") (pintype "passive"))
    )
    (net (code "47") (name "Net-(U2-CPL)") (class "Default")
      (node (ref "C9") (pin "2") (pinfunction "2_2") (pintype "passive"))
      (node (ref "U2") (pin "4") (pinfunction "CPL_4") (pintype "passive"))
    )
    (net (code "48") (name "Net-(U2-VCP)") (class "Default")
      (node (ref "C8") (pin "2") (pinfunction "2_2") (pintype "passive"))
      (node (ref "U2") (pin "2") (pinfunction "VCP_2") (pintype "power_in"))
    )
    (net (code "49") (name "VM") (class "Default")
      (node (ref "C10") (pin "1") (pinfunction "1_1") (pintype "passive"))
      (node (ref "C11") (pin "1") (pinfunction "+_1") (pintype "passive"))
      (node (ref "C12") (pin "1") (pinfunction "1_1") (pintype "passive"))
      (node (ref "C13") (pin "1") (pinfunction "+_1") (pintype "passive"))
      (node (ref "C16") (pin "2") (pinfunction "2_2") (pintype "passive"))
      (node (ref "C4") (pin "1") (pinfunction "1_1") (pintype "passive"))
      (node (ref "C5") (pin "1") (pinfunction "1_1") (pintype "passive"))
      (node (ref "C8") (pin "1") (pinfunction "1_1") (pintype "passive"))
      (node (ref "F1") (pin "2") (pinfunction "2_2") (pintype "passive"))
      (node (ref "Q1") (pin "5") (pinfunction "D_5") (pintype "passive"))
      (node (ref "Q1") (pin "6") (pinfunction "D_6") (pintype "passive"))
      (node (ref "Q1") (pin "7") (pinfunction "D_7") (pintype "passive"))
      (node (ref "Q1") (pin "8") (pinfunction "D_8") (pintype "passive"))
      (node (ref "Q3") (pin "5") (pinfunction "D_5") (pintype "passive"))
      (node (ref "Q3") (pin "6") (pinfunction "D_6") (pintype "passive"))
      (node (ref "Q3") (pin "7") (pinfunction "D_7") (pintype "passive"))
      (node (ref "Q3") (pin "8") (pinfunction "D_8") (pintype "passive"))
      (node (ref "R23") (pin "1") (pinfunction "1_1") (pintype "passive"))
      (node (ref "U2") (pin "1") (pinfunction "VM_1") (pintype "power_in"))
    )
    (net (code "50") (name "unconnected-(S1-Pad1)") (class "Default")
      (node (ref "S1") (pin "1") (pinfunction "1_1") (pintype "passive+no_connect"))
    )
    (net (code "51") (name "unconnected-(S1-Pad3)") (class "Default")
      (node (ref "S1") (pin "3") (pinfunction "3_3") (pintype "passive+no_connect"))
    )
    (net (code "52") (name "unconnected-(U1-P1.1{slash}TA0.0{slash}UCA0RXD{slash}UCA0SOMI{slash}A1{slash}CA1-Pad3)") (class "Default")
      (node (ref "U1") (pin "3") (pinfunction "P1.1/TA0.0/UCA0RXD/UCA0SOMI/A1/CA1_3") (pintype "bidirectional+no_connect"))
    )
    (net (code "53") (name "unconnected-(U1-P1.2{slash}TA0.1{slash}UCA0TXD{slash}UCA0SIMO{slash}A2{slash}CA2-Pad4)") (class "Default")
      (node (ref "U1") (pin "4") (pinfunction "P1.2/TA0.1/UCA0TXD/UCA0SIMO/A2/CA2_4") (pintype "bidirectional+no_connect"))
    )
    (net (code "54") (name "unconnected-(U1-P2.0{slash}TA1.0-Pad8)") (class "Default")
      (node (ref "U1") (pin "8") (pinfunction "P2.0/TA1.0_8") (pintype "bidirectional+no_connect"))
    )
    (net (code "55") (name "unconnected-(U1-P2.2{slash}TA1.1-Pad10)") (class "Default")
      (node (ref "U1") (pin "10") (pinfunction "P2.2/TA1.1_10") (pintype "bidirectional+no_connect"))
    )
    (net (code "56") (name "unconnected-(U1-P2.6{slash}XIN{slash}TA0.1-Pad19)") (class "Default")
      (node (ref "U1") (pin "19") (pinfunction "P2.6/XIN/TA0.1_19") (pintype "bidirectional+no_connect"))
    )
  )
)
